# bwaba.net
KiCad netlist of a schematic drawn in Altium Designer
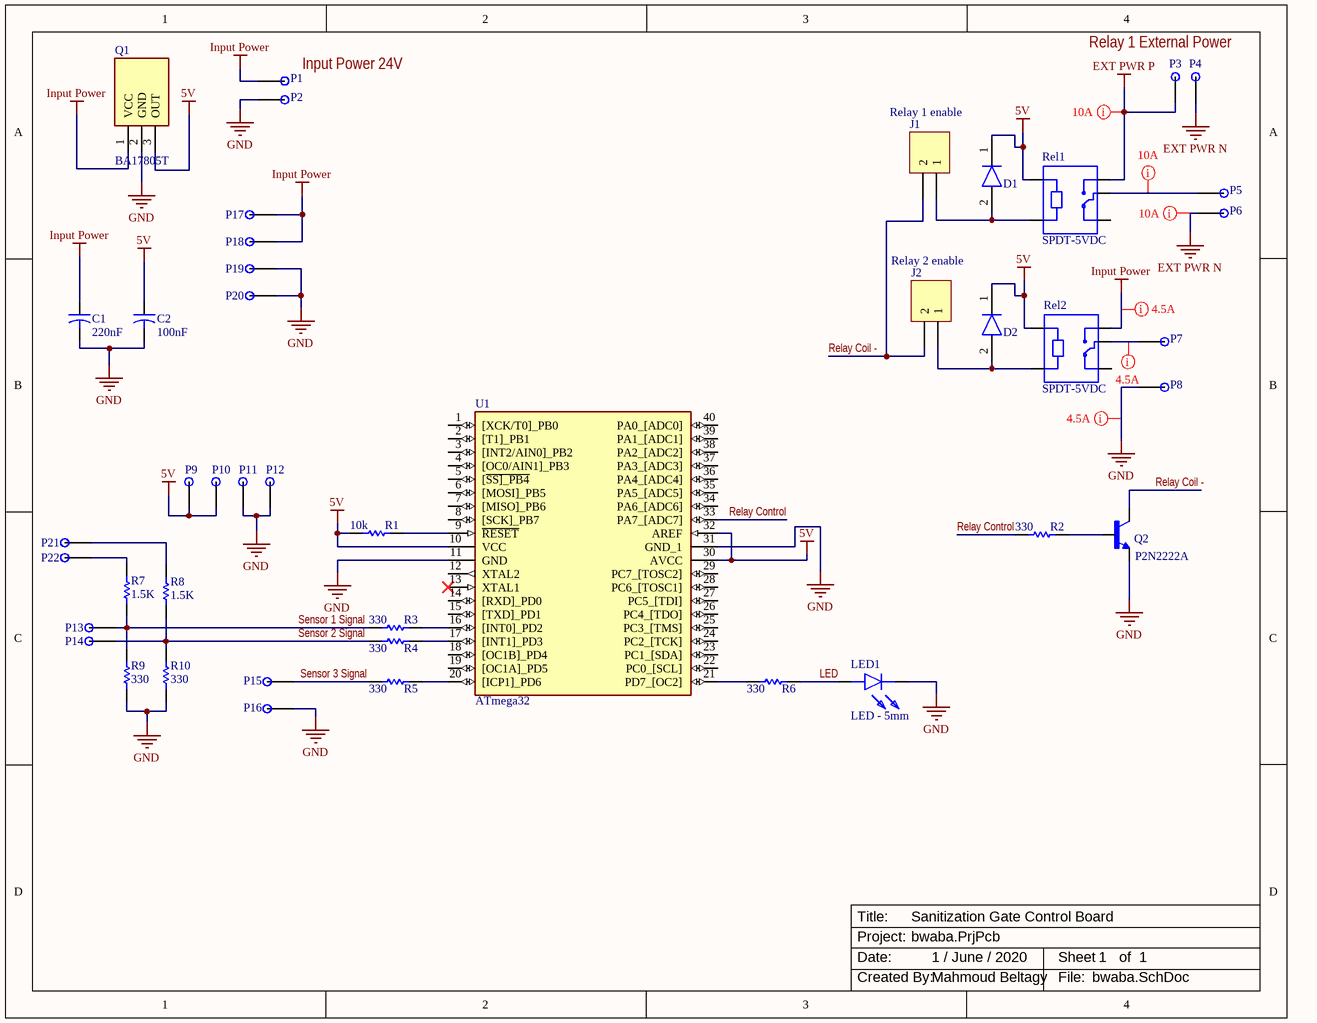
[diagram p0: bwaba.SchDoc]

(export (version "E")
  (design (tool "Eeschema 10.0.6"))
  (components
    (comp (ref "C1")
      (value "220nF")
      (footprint "CAPR5-4X5")
      (description "Capacitor")
      (fields (field (name "PUBLISHER") "Altium Limited"))
      (libsource (lib "Miscellaneous Devices") (part "Cap2"))
    )
    (comp (ref "C2")
      (value "100nF")
      (footprint "CAPR5-4X5")
      (description "Capacitor")
      (fields (field (name "PUBLISHER") "Altium Limited"))
      (libsource (lib "Miscellaneous Devices") (part "Cap2"))
    )
    (comp (ref "D1")
      (value "1N4007")
      (footprint "Diode Generic")
      (description "Diode")
      (fields (field (name "MOUSER PART NUMBER") "512-1N4007"))
      (libsource (lib "Belle_library") (part "1N4007"))
    )
    (comp (ref "D2")
      (value "1N4007")
      (footprint "Diode Generic")
      (description "Diode")
      (fields (field (name "MOUSER PART NUMBER") "512-1N4007"))
      (libsource (lib "Belle_library") (part "1N4007"))
    )
    (comp (ref "J1")
      (value "Relay 1 enable")
      (footprint "HDR1X2")
      (description "Header, 2-Pin")
      (fields (field (name "PUBLISHER") "Altium Limited"))
      (libsource (lib "Miscellaneous Connectors") (part "Header 2"))
    )
    (comp (ref "J2")
      (value "Relay 2 enable")
      (footprint "HDR1X2")
      (description "Header, 2-Pin")
      (fields (field (name "PUBLISHER") "Altium Limited"))
      (libsource (lib "Miscellaneous Connectors") (part "Header 2"))
    )
    (comp (ref "LED1")
      (value "LED - 5mm")
      (footprint "LED - 5mm")
      (description "LED")
      (fields (field (name "MANUFACTURER_PART_NUMBER") "L-53GD"))
      (libsource (lib "Belle_library") (part "LED - 5mm"))
    )
    (comp (ref "P1")
      (value "TH Pad - 2mm")
      (footprint "TH Pad - 2mm")
      (libsource (lib "Belle_library") (part "TH Pad - 2mm"))
    )
    (comp (ref "P2")
      (value "TH Pad - 2mm")
      (footprint "TH Pad - 2mm")
      (libsource (lib "Belle_library") (part "TH Pad - 2mm"))
    )
    (comp (ref "P3")
      (value "TH Pad - 2mm")
      (footprint "TH Pad - 2mm")
      (libsource (lib "Belle_library") (part "TH Pad - 2mm"))
    )
    (comp (ref "P4")
      (value "TH Pad - 2mm")
      (footprint "TH Pad - 2mm")
      (libsource (lib "Belle_library") (part "TH Pad - 2mm"))
    )
    (comp (ref "P5")
      (value "TH Pad - 2mm")
      (footprint "TH Pad - 2mm")
      (libsource (lib "Belle_library") (part "TH Pad - 2mm"))
    )
    (comp (ref "P6")
      (value "TH Pad - 2mm")
      (footprint "TH Pad - 2mm")
      (libsource (lib "Belle_library") (part "TH Pad - 2mm"))
    )
    (comp (ref "P7")
      (value "TH Pad - 2mm")
      (footprint "TH Pad - 2mm")
      (libsource (lib "Belle_library") (part "TH Pad - 2mm"))
    )
    (comp (ref "P8")
      (value "TH Pad - 2mm")
      (footprint "TH Pad - 2mm")
      (libsource (lib "Belle_library") (part "TH Pad - 2mm"))
    )
    (comp (ref "P9")
      (value "TH Pad - 2mm")
      (footprint "TH Pad - 2mm")
      (libsource (lib "Belle_library") (part "TH Pad - 2mm"))
    )
    (comp (ref "P10")
      (value "TH Pad - 2mm")
      (footprint "TH Pad - 2mm")
      (libsource (lib "Belle_library") (part "TH Pad - 2mm"))
    )
    (comp (ref "P11")
      (value "TH Pad - 2mm")
      (footprint "TH Pad - 2mm")
      (libsource (lib "Belle_library") (part "TH Pad - 2mm"))
    )
    (comp (ref "P12")
      (value "TH Pad - 2mm")
      (footprint "TH Pad - 2mm")
      (libsource (lib "Belle_library") (part "TH Pad - 2mm"))
    )
    (comp (ref "P13")
      (value "TH Pad - 2mm")
      (footprint "TH Pad - 2mm")
      (libsource (lib "Belle_library") (part "TH Pad - 2mm"))
    )
    (comp (ref "P14")
      (value "TH Pad - 2mm")
      (footprint "TH Pad - 2mm")
      (libsource (lib "Belle_library") (part "TH Pad - 2mm"))
    )
    (comp (ref "P15")
      (value "TH Pad - 2mm")
      (footprint "TH Pad - 2mm")
      (libsource (lib "Belle_library") (part "TH Pad - 2mm"))
    )
    (comp (ref "P16")
      (value "TH Pad - 2mm")
      (footprint "TH Pad - 2mm")
      (libsource (lib "Belle_library") (part "TH Pad - 2mm"))
    )
    (comp (ref "P17")
      (value "TH Pad - 2mm")
      (footprint "TH Pad - 2mm")
      (libsource (lib "Belle_library") (part "TH Pad - 2mm"))
    )
    (comp (ref "P18")
      (value "TH Pad - 2mm")
      (footprint "TH Pad - 2mm")
      (libsource (lib "Belle_library") (part "TH Pad - 2mm"))
    )
    (comp (ref "P19")
      (value "TH Pad - 2mm")
      (footprint "TH Pad - 2mm")
      (libsource (lib "Belle_library") (part "TH Pad - 2mm"))
    )
    (comp (ref "P20")
      (value "TH Pad - 2mm")
      (footprint "TH Pad - 2mm")
      (libsource (lib "Belle_library") (part "TH Pad - 2mm"))
    )
    (comp (ref "P21")
      (value "TH Pad - 2mm")
      (footprint "TH Pad - 2mm")
      (libsource (lib "Belle_library") (part "TH Pad - 2mm"))
    )
    (comp (ref "P22")
      (value "TH Pad - 2mm")
      (footprint "TH Pad - 2mm")
      (libsource (lib "Belle_library") (part "TH Pad - 2mm"))
    )
    (comp (ref "Q1")
      (value "BA17805T")
      (footprint "SamacSys:TO254P480X1010X2280-3P")
      (description "Voltage Regulator")
      (fields (field (name "MOUSER PART NUMBER") "755-BA17805T"))
      (libsource (lib "Belle_library") (part "BA17805T"))
    )
    (comp (ref "Q2")
      (value "P2N2222A")
      (footprint "TO92")
      (description "Transitor BJT_ NPN 40V 600mA 300 MHz 625mW TO-92-3")
      (fields (field (name "MF") "ON Semiconductor"))
      (libsource (lib "Belle_library") (part "P2N2222A"))
    )
    (comp (ref "R1")
      (value "10k")
      (footprint "AXIAL-0.3")
      (description "Resistor")
      (fields (field (name "PUBLISHER") "Altium Limited"))
      (libsource (lib "Miscellaneous Devices") (part "Res1"))
    )
    (comp (ref "R2")
      (value "330")
      (footprint "AXIAL-0.3")
      (description "Resistor")
      (fields (field (name "PUBLISHER") "Altium Limited"))
      (libsource (lib "Miscellaneous Devices") (part "Res1"))
    )
    (comp (ref "R3")
      (value "330")
      (footprint "AXIAL-0.3")
      (description "Resistor")
      (fields (field (name "PUBLISHER") "Altium Limited"))
      (libsource (lib "Miscellaneous Devices") (part "Res1"))
    )
    (comp (ref "R4")
      (value "330")
      (footprint "AXIAL-0.3")
      (description "Resistor")
      (fields (field (name "PUBLISHER") "Altium Limited"))
      (libsource (lib "Miscellaneous Devices") (part "Res1"))
    )
    (comp (ref "R5")
      (value "330")
      (footprint "AXIAL-0.3")
      (description "Resistor")
      (fields (field (name "PUBLISHER") "Altium Limited"))
      (libsource (lib "Miscellaneous Devices") (part "Res1"))
    )
    (comp (ref "R6")
      (value "330")
      (footprint "AXIAL-0.3")
      (description "Resistor")
      (fields (field (name "PUBLISHER") "Altium Limited"))
      (libsource (lib "Miscellaneous Devices") (part "Res1"))
    )
    (comp (ref "R7")
      (value "1.5K")
      (footprint "AXIAL-0.3")
      (description "Resistor")
      (fields (field (name "PUBLISHER") "Altium Limited"))
      (libsource (lib "Miscellaneous Devices") (part "Res1"))
    )
    (comp (ref "R8")
      (value "1.5K")
      (footprint "AXIAL-0.3")
      (description "Resistor")
      (fields (field (name "PUBLISHER") "Altium Limited"))
      (libsource (lib "Miscellaneous Devices") (part "Res1"))
    )
    (comp (ref "R9")
      (value "330")
      (footprint "AXIAL-0.3")
      (description "Resistor")
      (fields (field (name "PUBLISHER") "Altium Limited"))
      (libsource (lib "Miscellaneous Devices") (part "Res1"))
    )
    (comp (ref "R10")
      (value "330")
      (footprint "AXIAL-0.3")
      (description "Resistor")
      (fields (field (name "PUBLISHER") "Altium Limited"))
      (libsource (lib "Miscellaneous Devices") (part "Res1"))
    )
    (comp (ref "Rel1")
      (value "SPDT-5VDC")
      (footprint "SRD-5VDC")
      (description "Relay")
      (libsource (lib "Belle_library") (part "Relay-SRD-5VDC"))
    )
    (comp (ref "Rel2")
      (value "SPDT-5VDC")
      (footprint "SRD-5VDC")
      (description "Relay")
      (libsource (lib "Belle_library") (part "Relay-SRD-5VDC"))
    )
    (comp (ref "U1")
      (value "ATmega32")
      (footprint "DIP1556W56P254L5232H483Q40N")
      (description "AVR ATmega Microcontroller IC 8-Bit 16MHz 32KB _16K x 16_ FLASH 40-PDIP")
      (fields
        (field (name "MOUSER2 PART NUMBER") "556-ATMEGA32-16PU")
        (field (name "MANUFACTURER_PART_NUMBER") "ATMEGA32-16PU")
      )
      (libsource (lib "Belle_library") (part "ATMEGA32-16PU_1"))
    )
  )
  (nets
    (net (code "1") (name "/LED") (class "Default")
      (node (ref "LED1") (pin "1") (pinfunction "A_1") (pintype "passive"))
      (node (ref "R6") (pin "2") (pinfunction "2_2") (pintype "passive"))
    )
    (net (code "2") (name "/Relay Coil -") (class "Default")
      (node (ref "J1") (pin "2") (pinfunction "2_2") (pintype "passive"))
      (node (ref "J2") (pin "2") (pinfunction "2_2") (pintype "passive"))
      (node (ref "Q2") (pin "3") (pinfunction "C_3") (pintype "passive"))
    )
    (net (code "3") (name "/Relay Control") (class "Default")
      (node (ref "R2") (pin "1") (pinfunction "1_1") (pintype "passive"))
      (node (ref "U1") (pin "33") (pinfunction "PA7_[ADC7]_33") (pintype "bidirectional"))
    )
    (net (code "4") (name "/Sensor 1 Signal") (class "Default")
      (node (ref "P13") (pin "1") (pinfunction "P_1") (pintype "passive"))
      (node (ref "R3") (pin "1") (pinfunction "1_1") (pintype "passive"))
      (node (ref "R7") (pin "1") (pinfunction "1_1") (pintype "passive"))
      (node (ref "R9") (pin "2") (pinfunction "2_2") (pintype "passive"))
    )
    (net (code "5") (name "/Sensor 2 Signal") (class "Default")
      (node (ref "P14") (pin "1") (pinfunction "P_1") (pintype "passive"))
      (node (ref "R10") (pin "2") (pinfunction "2_2") (pintype "passive"))
      (node (ref "R4") (pin "1") (pinfunction "1_1") (pintype "passive"))
      (node (ref "R8") (pin "1") (pinfunction "1_1") (pintype "passive"))
    )
    (net (code "6") (name "/Sensor 3 Signal") (class "Default")
      (node (ref "P15") (pin "1") (pinfunction "P_1") (pintype "passive"))
      (node (ref "R5") (pin "1") (pinfunction "1_1") (pintype "passive"))
    )
    (net (code "7") (name "5V") (class "Default")
      (node (ref "C2") (pin "1") (pinfunction "1_1") (pintype "passive"))
      (node (ref "D1") (pin "1") (pinfunction "K_1") (pintype "passive"))
      (node (ref "D2") (pin "1") (pinfunction "K_1") (pintype "passive"))
      (node (ref "P10") (pin "1") (pinfunction "P_1") (pintype "passive"))
      (node (ref "P9") (pin "1") (pinfunction "P_1") (pintype "passive"))
      (node (ref "Q1") (pin "3") (pinfunction "OUT_3") (pintype "power_in"))
      (node (ref "R1") (pin "1") (pinfunction "1_1") (pintype "passive"))
      (node (ref "Rel1") (pin "A1") (pinfunction "A1_A1") (pintype "passive"))
      (node (ref "Rel2") (pin "A1") (pinfunction "A1_A1") (pintype "passive"))
      (node (ref "U1") (pin "10") (pinfunction "VCC_10") (pintype "power_in"))
      (node (ref "U1") (pin "30") (pinfunction "AVCC_30") (pintype "power_in"))
      (node (ref "U1") (pin "32") (pinfunction "AREF_32") (pintype "input"))
    )
    (net (code "8") (name "EXT PWR N") (class "Default")
      (node (ref "P4") (pin "1") (pinfunction "P_1") (pintype "passive"))
      (node (ref "P6") (pin "1") (pinfunction "P_1") (pintype "passive"))
    )
    (net (code "9") (name "EXT PWR P") (class "Default")
      (node (ref "P3") (pin "1") (pinfunction "P_1") (pintype "passive"))
      (node (ref "Rel1") (pin "NO") (pinfunction "NO_NO") (pintype "passive"))
    )
    (net (code "10") (name "GND") (class "Default")
      (node (ref "C1") (pin "2") (pinfunction "2_2") (pintype "passive"))
      (node (ref "C2") (pin "2") (pinfunction "2_2") (pintype "passive"))
      (node (ref "LED1") (pin "2") (pinfunction "K_2") (pintype "passive"))
      (node (ref "P11") (pin "1") (pinfunction "P_1") (pintype "passive"))
      (node (ref "P12") (pin "1") (pinfunction "P_1") (pintype "passive"))
      (node (ref "P16") (pin "1") (pinfunction "P_1") (pintype "passive"))
      (node (ref "P19") (pin "1") (pinfunction "P_1") (pintype "passive"))
      (node (ref "P2") (pin "1") (pinfunction "P_1") (pintype "passive"))
      (node (ref "P20") (pin "1") (pinfunction "P_1") (pintype "passive"))
      (node (ref "P8") (pin "1") (pinfunction "P_1") (pintype "passive"))
      (node (ref "Q1") (pin "2") (pinfunction "GND_2") (pintype "power_in"))
      (node (ref "Q2") (pin "1") (pinfunction "E_1") (pintype "passive"))
      (node (ref "R10") (pin "1") (pinfunction "1_1") (pintype "passive"))
      (node (ref "R9") (pin "1") (pinfunction "1_1") (pintype "passive"))
      (node (ref "U1") (pin "11") (pinfunction "GND_11") (pintype "power_in"))
      (node (ref "U1") (pin "31") (pinfunction "GND_1_31") (pintype "power_in"))
    )
    (net (code "11") (name "Input Power") (class "Default")
      (node (ref "C1") (pin "1") (pinfunction "1_1") (pintype "passive"))
      (node (ref "P1") (pin "1") (pinfunction "P_1") (pintype "passive"))
      (node (ref "P17") (pin "1") (pinfunction "P_1") (pintype "passive"))
      (node (ref "P18") (pin "1") (pinfunction "P_1") (pintype "passive"))
      (node (ref "Q1") (pin "1") (pinfunction "VCC_1") (pintype "power_in"))
      (node (ref "Rel2") (pin "NO") (pinfunction "NO_NO") (pintype "passive"))
    )
    (net (code "12") (name "Net-(D1-A)") (class "Default")
      (node (ref "D1") (pin "2") (pinfunction "A_2") (pintype "passive"))
      (node (ref "J1") (pin "1") (pinfunction "1_1") (pintype "passive"))
      (node (ref "Rel1") (pin "A2") (pinfunction "A2_A2") (pintype "passive"))
    )
    (net (code "13") (name "Net-(D2-A)") (class "Default")
      (node (ref "D2") (pin "2") (pinfunction "A_2") (pintype "passive"))
      (node (ref "J2") (pin "1") (pinfunction "1_1") (pintype "passive"))
      (node (ref "Rel2") (pin "A2") (pinfunction "A2_A2") (pintype "passive"))
    )
    (net (code "14") (name "Net-(P5-P)") (class "Default")
      (node (ref "P5") (pin "1") (pinfunction "P_1") (pintype "passive"))
      (node (ref "Rel1") (pin "COM") (pinfunction "COM_COM") (pintype "passive"))
    )
    (net (code "15") (name "Net-(P7-P)") (class "Default")
      (node (ref "P7") (pin "1") (pinfunction "P_1") (pintype "passive"))
      (node (ref "Rel2") (pin "COM") (pinfunction "COM_COM") (pintype "passive"))
    )
    (net (code "16") (name "Net-(P21-P)") (class "Default")
      (node (ref "P21") (pin "1") (pinfunction "P_1") (pintype "passive"))
      (node (ref "R8") (pin "2") (pinfunction "2_2") (pintype "passive"))
    )
    (net (code "17") (name "Net-(P22-P)") (class "Default")
      (node (ref "P22") (pin "1") (pinfunction "P_1") (pintype "passive"))
      (node (ref "R7") (pin "2") (pinfunction "2_2") (pintype "passive"))
    )
    (net (code "18") (name "Net-(Q2-B)") (class "Default")
      (node (ref "Q2") (pin "2") (pinfunction "B_2") (pintype "passive"))
      (node (ref "R2") (pin "2") (pinfunction "2_2") (pintype "passive"))
    )
    (net (code "19") (name "Net-(U1-PD7_[OC2])") (class "Default")
      (node (ref "R6") (pin "1") (pinfunction "1_1") (pintype "passive"))
      (node (ref "U1") (pin "21") (pinfunction "PD7_[OC2]_21") (pintype "bidirectional"))
    )
    (net (code "20") (name "Net-(U1-[ICP1]_PD6)") (class "Default")
      (node (ref "R5") (pin "2") (pinfunction "2_2") (pintype "passive"))
      (node (ref "U1") (pin "20") (pinfunction "[ICP1]_PD6_20") (pintype "bidirectional"))
    )
    (net (code "21") (name "Net-(U1-[INT0]_PD2)") (class "Default")
      (node (ref "R3") (pin "2") (pinfunction "2_2") (pintype "passive"))
      (node (ref "U1") (pin "16") (pinfunction "[INT0]_PD2_16") (pintype "bidirectional"))
    )
    (net (code "22") (name "Net-(U1-[INT1]_PD3)") (class "Default")
      (node (ref "R4") (pin "2") (pinfunction "2_2") (pintype "passive"))
      (node (ref "U1") (pin "17") (pinfunction "[INT1]_PD3_17") (pintype "bidirectional"))
    )
    (net (code "23") (name "Net-(U1-~{RESET})") (class "Default")
      (node (ref "R1") (pin "2") (pinfunction "2_2") (pintype "passive"))
      (node (ref "U1") (pin "9") (pinfunction "~{RESET}_9") (pintype "input"))
    )
    (net (code "24") (name "unconnected-(Rel1-PadNC)") (class "Default")
      (node (ref "Rel1") (pin "NC") (pinfunction "NC_NC") (pintype "passive"))
    )
    (net (code "25") (name "unconnected-(Rel2-PadNC)") (class "Default")
      (node (ref "Rel2") (pin "NC") (pinfunction "NC_NC") (pintype "passive"))
    )
    (net (code "26") (name "unconnected-(U1-PA0_[ADC0]-Pad40)") (class "Default")
      (node (ref "U1") (pin "40") (pinfunction "PA0_[ADC0]_40") (pintype "bidirectional"))
    )
    (net (code "27") (name "unconnected-(U1-PA1_[ADC1]-Pad39)") (class "Default")
      (node (ref "U1") (pin "39") (pinfunction "PA1_[ADC1]_39") (pintype "bidirectional"))
    )
    (net (code "28") (name "unconnected-(U1-PA2_[ADC2]-Pad38)") (class "Default")
      (node (ref "U1") (pin "38") (pinfunction "PA2_[ADC2]_38") (pintype "bidirectional"))
    )
    (net (code "29") (name "unconnected-(U1-PA3_[ADC3]-Pad37)") (class "Default")
      (node (ref "U1") (pin "37") (pinfunction "PA3_[ADC3]_37") (pintype "bidirectional"))
    )
    (net (code "30") (name "unconnected-(U1-PA4_[ADC4]-Pad36)") (class "Default")
      (node (ref "U1") (pin "36") (pinfunction "PA4_[ADC4]_36") (pintype "bidirectional"))
    )
    (net (code "31") (name "unconnected-(U1-PA5_[ADC5]-Pad35)") (class "Default")
      (node (ref "U1") (pin "35") (pinfunction "PA5_[ADC5]_35") (pintype "bidirectional"))
    )
    (net (code "32") (name "unconnected-(U1-PA6_[ADC6]-Pad34)") (class "Default")
      (node (ref "U1") (pin "34") (pinfunction "PA6_[ADC6]_34") (pintype "bidirectional"))
    )
    (net (code "33") (name "unconnected-(U1-PC0_[SCL]-Pad22)") (class "Default")
      (node (ref "U1") (pin "22") (pinfunction "PC0_[SCL]_22") (pintype "bidirectional"))
    )
    (net (code "34") (name "unconnected-(U1-PC1_[SDA]-Pad23)") (class "Default")
      (node (ref "U1") (pin "23") (pinfunction "PC1_[SDA]_23") (pintype "bidirectional"))
    )
    (net (code "35") (name "unconnected-(U1-PC2_[TCK]-Pad24)") (class "Default")
      (node (ref "U1") (pin "24") (pinfunction "PC2_[TCK]_24") (pintype "bidirectional"))
    )
    (net (code "36") (name "unconnected-(U1-PC3_[TMS]-Pad25)") (class "Default")
      (node (ref "U1") (pin "25") (pinfunction "PC3_[TMS]_25") (pintype "bidirectional"))
    )
    (net (code "37") (name "unconnected-(U1-PC4_[TDO]-Pad26)") (class "Default")
      (node (ref "U1") (pin "26") (pinfunction "PC4_[TDO]_26") (pintype "bidirectional"))
    )
    (net (code "38") (name "unconnected-(U1-PC5_[TDI]-Pad27)") (class "Default")
      (node (ref "U1") (pin "27") (pinfunction "PC5_[TDI]_27") (pintype "bidirectional"))
    )
    (net (code "39") (name "unconnected-(U1-PC6_[TOSC1]-Pad28)") (class "Default")
      (node (ref "U1") (pin "28") (pinfunction "PC6_[TOSC1]_28") (pintype "bidirectional"))
    )
    (net (code "40") (name "unconnected-(U1-PC7_[TOSC2]-Pad29)") (class "Default")
      (node (ref "U1") (pin "29") (pinfunction "PC7_[TOSC2]_29") (pintype "bidirectional"))
    )
    (net (code "41") (name "unconnected-(U1-XTAL1-Pad13)") (class "Default")
      (node (ref "U1") (pin "13") (pinfunction "XTAL1_13") (pintype "input+no_connect"))
    )
    (net (code "42") (name "unconnected-(U1-XTAL2-Pad12)") (class "Default")
      (node (ref "U1") (pin "12") (pinfunction "XTAL2_12") (pintype "output"))
    )
    (net (code "43") (name "unconnected-(U1-[INT2{slash}AIN0]_PB2-Pad3)") (class "Default")
      (node (ref "U1") (pin "3") (pinfunction "[INT2/AIN0]_PB2_3") (pintype "bidirectional"))
    )
    (net (code "44") (name "unconnected-(U1-[MISO]_PB6-Pad7)") (class "Default")
      (node (ref "U1") (pin "7") (pinfunction "[MISO]_PB6_7") (pintype "bidirectional"))
    )
    (net (code "45") (name "unconnected-(U1-[MOSI]_PB5-Pad6)") (class "Default")
      (node (ref "U1") (pin "6") (pinfunction "[MOSI]_PB5_6") (pintype "bidirectional"))
    )
    (net (code "46") (name "unconnected-(U1-[OC0{slash}AIN1]_PB3-Pad4)") (class "Default")
      (node (ref "U1") (pin "4") (pinfunction "[OC0/AIN1]_PB3_4") (pintype "bidirectional"))
    )
    (net (code "47") (name "unconnected-(U1-[OC1A]_PD5-Pad19)") (class "Default")
      (node (ref "U1") (pin "19") (pinfunction "[OC1A]_PD5_19") (pintype "bidirectional"))
    )
    (net (code "48") (name "unconnected-(U1-[OC1B]_PD4-Pad18)") (class "Default")
      (node (ref "U1") (pin "18") (pinfunction "[OC1B]_PD4_18") (pintype "bidirectional"))
    )
    (net (code "49") (name "unconnected-(U1-[RXD]_PD0-Pad14)") (class "Default")
      (node (ref "U1") (pin "14") (pinfunction "[RXD]_PD0_14") (pintype "bidirectional"))
    )
    (net (code "50") (name "unconnected-(U1-[SCK]_PB7-Pad8)") (class "Default")
      (node (ref "U1") (pin "8") (pinfunction "[SCK]_PB7_8") (pintype "bidirectional"))
    )
    (net (code "51") (name "unconnected-(U1-[T1]_PB1-Pad2)") (class "Default")
      (node (ref "U1") (pin "2") (pinfunction "[T1]_PB1_2") (pintype "bidirectional"))
    )
    (net (code "52") (name "unconnected-(U1-[TXD]_PD1-Pad15)") (class "Default")
      (node (ref "U1") (pin "15") (pinfunction "[TXD]_PD1_15") (pintype "bidirectional"))
    )
    (net (code "53") (name "unconnected-(U1-[XCK{slash}T0]_PB0-Pad1)") (class "Default")
      (node (ref "U1") (pin "1") (pinfunction "[XCK/T0]_PB0_1") (pintype "bidirectional"))
    )
    (net (code "54") (name "unconnected-(U1-[~{SS]_PB4}-Pad5)") (class "Default")
      (node (ref "U1") (pin "5") (pinfunction "[~{SS]_PB4}_5") (pintype "bidirectional"))
    )
  )
)
